# samll_car.net
KiCad netlist of a schematic drawn in Altium Designer
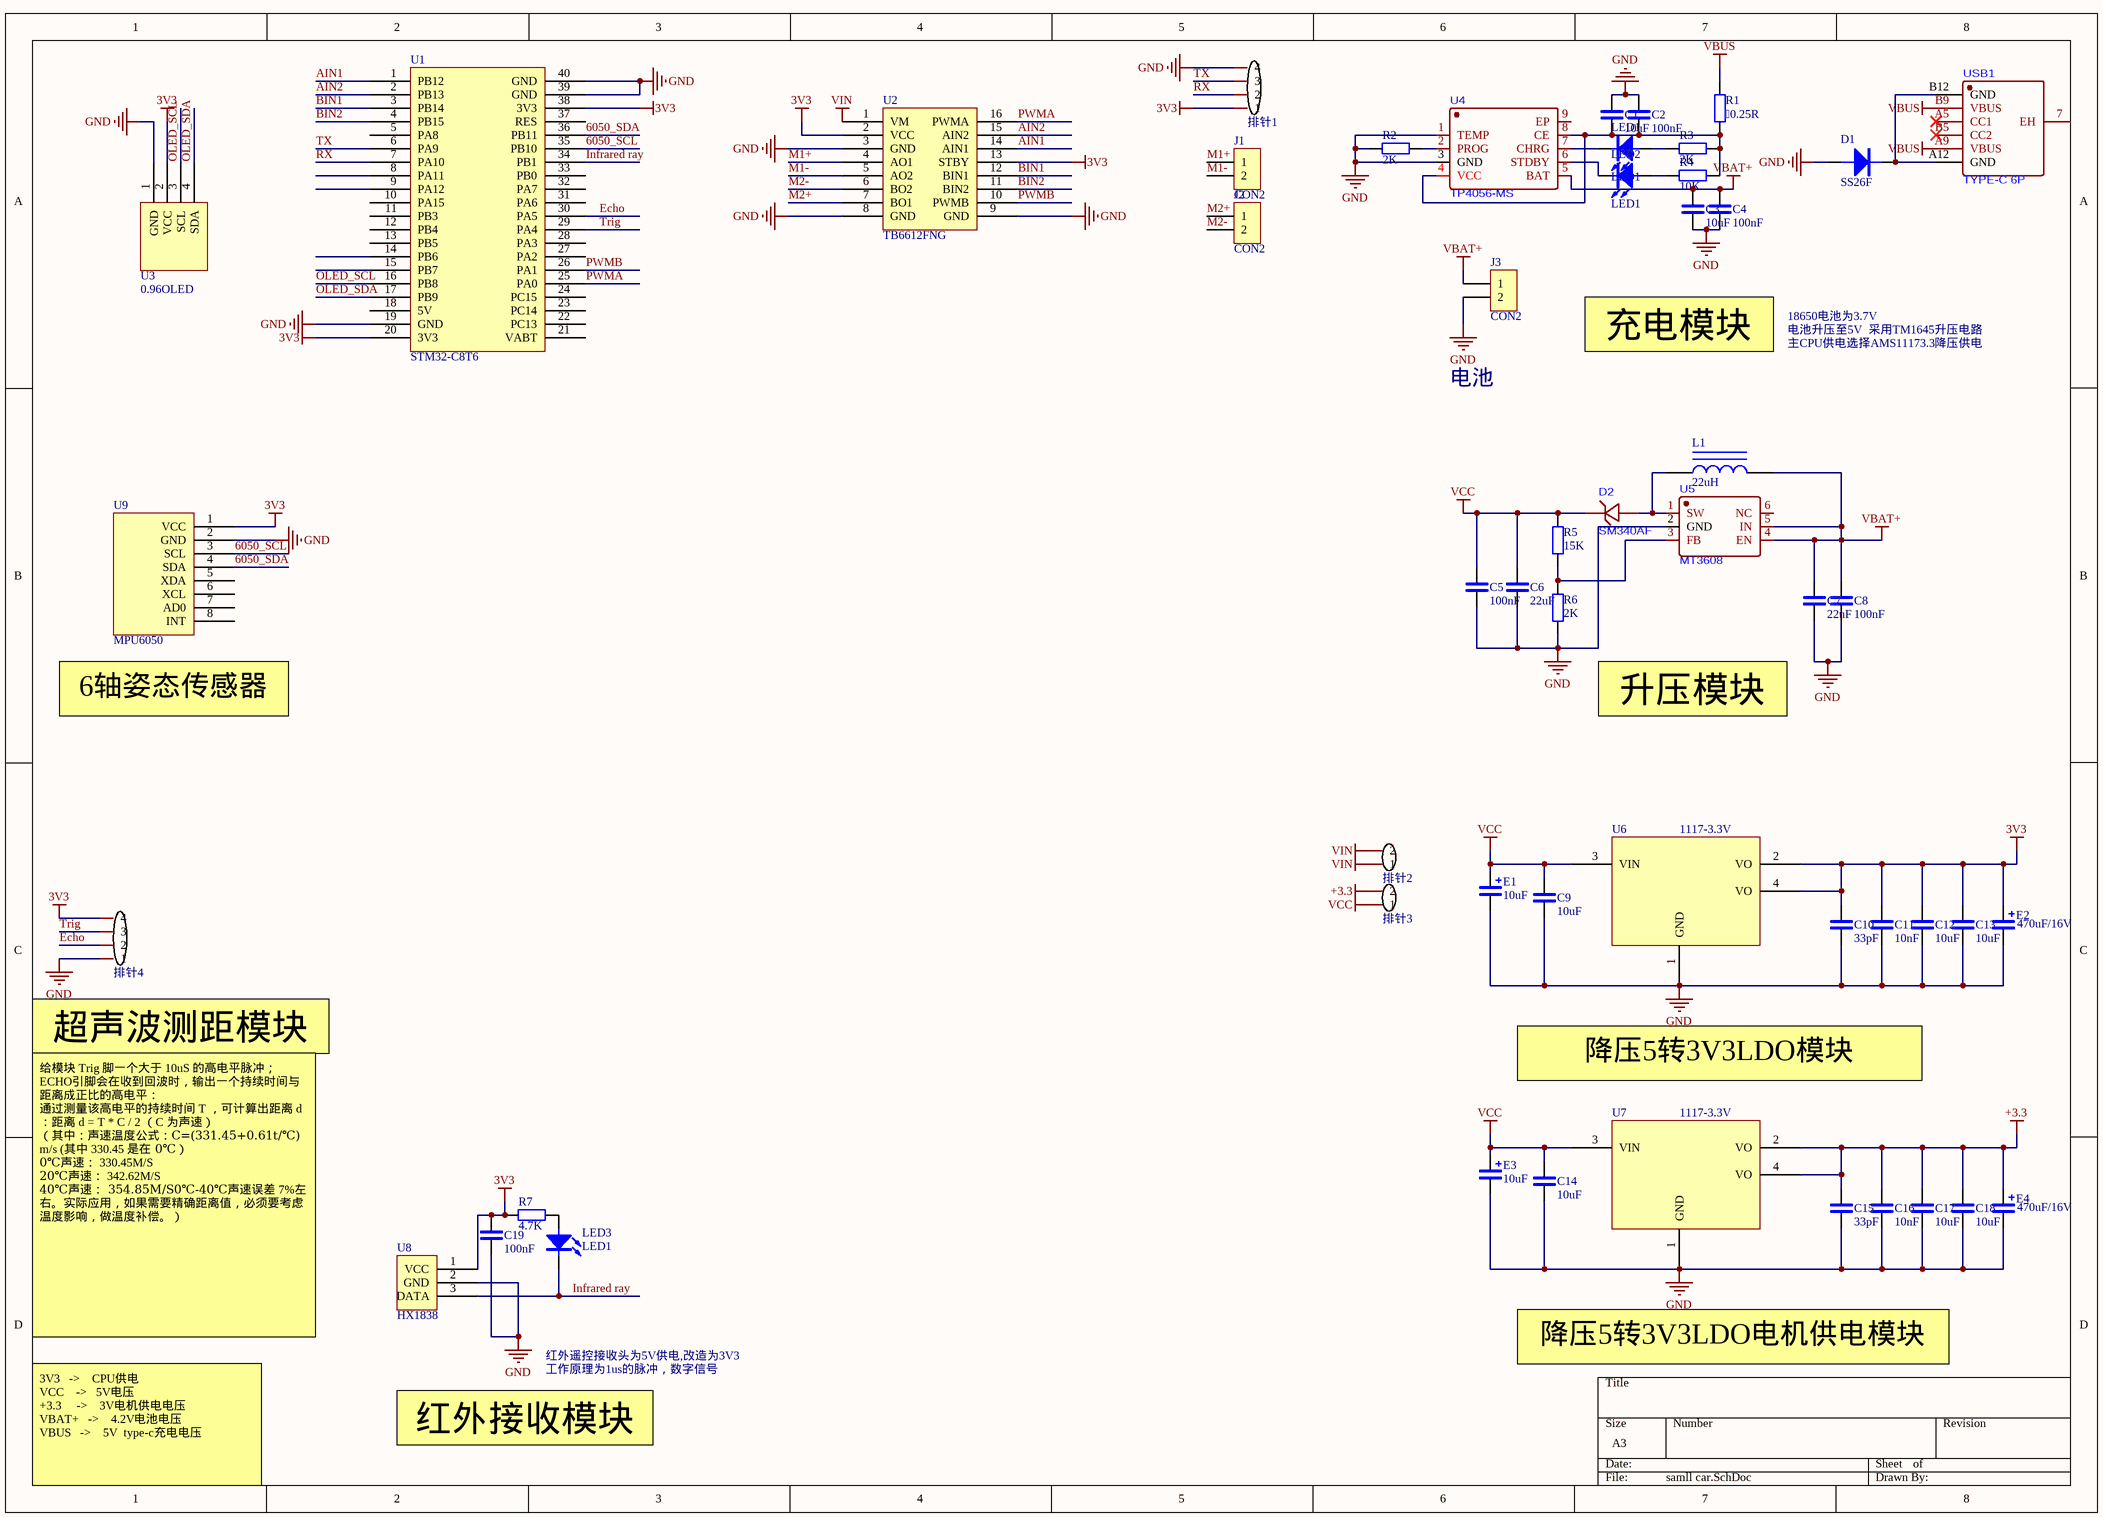
[diagram p0: samll car.SchDoc]

(export (version "E")
  (design (tool "Eeschema 10.0.6"))
  (components
    (comp (ref "C1")
      (value "10uF")
      (footprint "C0603")
      (description "Capacitor")
      (libsource (lib "General") (part "CAP"))
    )
    (comp (ref "C2")
      (value "100nF")
      (footprint "C0603")
      (description "Capacitor")
      (libsource (lib "General") (part "CAP"))
    )
    (comp (ref "C3")
      (value "10uF")
      (footprint "C0603")
      (description "Capacitor")
      (libsource (lib "General") (part "CAP"))
    )
    (comp (ref "C4")
      (value "100nF")
      (footprint "C0603")
      (description "Capacitor")
      (libsource (lib "General") (part "CAP"))
    )
    (comp (ref "C5")
      (value "100nF")
      (footprint "C0603")
      (description "Capacitor")
      (libsource (lib "General") (part "CAP"))
    )
    (comp (ref "C6")
      (value "22uF")
      (footprint "C0603")
      (description "Capacitor")
      (libsource (lib "General") (part "CAP"))
    )
    (comp (ref "C7")
      (value "22uF")
      (footprint "C0603")
      (description "Capacitor")
      (libsource (lib "General") (part "CAP"))
    )
    (comp (ref "C8")
      (value "100nF")
      (footprint "C0603")
      (description "Capacitor")
      (libsource (lib "General") (part "CAP"))
    )
    (comp (ref "C9")
      (value "10uF")
      (footprint "C0603")
      (description "Capacitor")
      (libsource (lib "General") (part "CAP"))
    )
    (comp (ref "C10")
      (value "33pF")
      (footprint "C0603")
      (description "Capacitor")
      (libsource (lib "General") (part "CAP"))
    )
    (comp (ref "C11")
      (value "10nF")
      (footprint "C0603")
      (description "Capacitor")
      (libsource (lib "General") (part "CAP"))
    )
    (comp (ref "C12")
      (value "10uF")
      (footprint "C0603")
      (description "Capacitor")
      (libsource (lib "General") (part "CAP"))
    )
    (comp (ref "C13")
      (value "10uF")
      (footprint "C0603")
      (description "Capacitor")
      (libsource (lib "General") (part "CAP"))
    )
    (comp (ref "C14")
      (value "10uF")
      (footprint "C0603")
      (description "Capacitor")
      (libsource (lib "General") (part "CAP"))
    )
    (comp (ref "C15")
      (value "33pF")
      (footprint "C0603")
      (description "Capacitor")
      (libsource (lib "General") (part "CAP"))
    )
    (comp (ref "C16")
      (value "10nF")
      (footprint "C0603")
      (description "Capacitor")
      (libsource (lib "General") (part "CAP"))
    )
    (comp (ref "C17")
      (value "10uF")
      (footprint "C0603")
      (description "Capacitor")
      (libsource (lib "General") (part "CAP"))
    )
    (comp (ref "C18")
      (value "10uF")
      (footprint "C0603")
      (description "Capacitor")
      (libsource (lib "General") (part "CAP"))
    )
    (comp (ref "C19")
      (value "100nF")
      (footprint "C0603")
      (description "Capacitor")
      (libsource (lib "General") (part "CAP"))
    )
    (comp (ref "D1")
      (value "SS26F")
      (footprint "SMAF")
      (description "Diode")
      (libsource (lib "莫尼库") (part "1N4007"))
    )
    (comp (ref "D2") (value "SM340AF") (footprint "SMA-FL-RD") (libsource (lib "莫尼库") (part "F1M")))
    (comp (ref "E1")
      (value "10uF")
      (footprint "CAP-TANTALUM-A")
      (description "Tantalum Capacitor")
      (libsource (lib "General") (part "CAP-TANTALUM"))
    )
    (comp (ref "E2")
      (value "470uF/16V")
      (footprint "CAP-TH_BD6.0-P2.50-D0.5-FD")
      (description "Tantalum Capacitor")
      (libsource (lib "General") (part "CAP-TANTALUM"))
    )
    (comp (ref "E3")
      (value "10uF")
      (footprint "CAP-TANTALUM-A")
      (description "Tantalum Capacitor")
      (libsource (lib "General") (part "CAP-TANTALUM"))
    )
    (comp (ref "E4")
      (value "470uF/16V")
      (footprint "CAP-TH_BD6.0-P2.50-D0.5-FD")
      (description "Tantalum Capacitor")
      (libsource (lib "General") (part "CAP-TANTALUM"))
    )
    (comp (ref "J1")
      (value "CON2")
      (footprint "XH2.54-2PZZ")
      (description "Connector")
      (libsource (lib "莫尼库") (part "CON2"))
    )
    (comp (ref "J2")
      (value "CON2")
      (footprint "XH2.54-2PZZ")
      (description "Connector")
      (libsource (lib "莫尼库") (part "CON2"))
    )
    (comp (ref "J3")
      (value "CON2")
      (footprint "XH2.54-2PZZ")
      (description "Connector")
      (libsource (lib "莫尼库") (part "CON2"))
    )
    (comp (ref "L1")
      (value "22uH")
      (footprint "IND-SMD_L5.0-W5.0")
      (description "Magnetic-Core Inductor")
      (fields (field (name "PUBLISHER") "Altium Limited"))
      (libsource (lib "莫尼库") (part "Inductor Iron"))
    )
    (comp (ref "LED1")
      (value "LED1")
      (footprint "LED-0603")
      (description "单色发光二极管")
      (libsource (lib "莫尼库") (part "LED1"))
    )
    (comp (ref "LED2")
      (value "LED1")
      (footprint "LED-0603")
      (description "单色发光二极管")
      (libsource (lib "莫尼库") (part "LED1"))
    )
    (comp (ref "LED3")
      (value "LED1")
      (footprint "LED-0603")
      (description "单色发光二极管")
      (libsource (lib "莫尼库") (part "LED1"))
    )
    (comp (ref "R1")
      (value "0.25R")
      (footprint "R1206")
      (description "Resistor")
      (libsource (lib "General") (part "RES"))
    )
    (comp (ref "R2")
      (value "2K")
      (footprint "R0603")
      (description "Resistor")
      (libsource (lib "") (part "RES_2"))
    )
    (comp (ref "R3")
      (value "2K")
      (footprint "R0603")
      (description "Resistor")
      (libsource (lib "") (part "RES_1"))
    )
    (comp (ref "R4")
      (value "10K")
      (footprint "R0603")
      (description "Resistor")
      (libsource (lib "") (part "RES_1"))
    )
    (comp (ref "R5")
      (value "15K")
      (footprint "R0603")
      (description "Resistor")
      (libsource (lib "General") (part "RES"))
    )
    (comp (ref "R6")
      (value "2K")
      (footprint "R0603")
      (description "Resistor")
      (libsource (lib "General") (part "RES"))
    )
    (comp (ref "R7")
      (value "4.7K")
      (footprint "R0603")
      (description "Resistor")
      (libsource (lib "") (part "RES_1"))
    )
    (comp (ref "U1")
      (value "STM32-C8T6")
      (footprint "STM32-C8T6")
      (libsource (lib "small car") (part "STM32-C8T6"))
    )
    (comp (ref "U2")
      (value "TB6612FNG")
      (footprint "TB6612FNG")
      (libsource (lib "small car") (part "TB6612FNG"))
    )
    (comp (ref "U3")
      (value "0.96OLED")
      (footprint "0.96OLED")
      (libsource (lib "small car") (part "0.96OLED"))
    )
    (comp (ref "U4") (value "TP4056-MS") (footprint "SOP-8-TL-EP") (libsource (lib "莫尼库") (part "TP4056-MS")))
    (comp (ref "U5") (value "MT3608") (footprint "SOT-23-6") (libsource (lib "莫尼库") (part "MT3608")))
    (comp (ref "U6")
      (value "1117-3.3V")
      (footprint "SOT-223")
      (description "Linear Regulator")
      (libsource (lib "General") (part "1117"))
    )
    (comp (ref "U7")
      (value "1117-3.3V")
      (footprint "SOT-223")
      (description "Linear Regulator")
      (libsource (lib "General") (part "1117"))
    )
    (comp (ref "U8") (value "HX1838") (footprint "VS/HX1838B") (libsource (lib "small car") (part "HX1838")))
    (comp (ref "U9") (value "MPU6050") (footprint "MPU6050") (libsource (lib "small car") (part "MPU6050")))
    (comp (ref "USB1") (value "TYPE-C 6P") (footprint "TYPE-C-6P") (libsource (lib "莫尼库") (part "TYPE-C 6P")))
    (comp (ref "排针1") (value "4P 排针") (footprint "XH2.54-1*4") (libsource (lib "莫尼库") (part "4P 排针")))
    (comp (ref "排针2") (value "2P 排针") (footprint "XH2.54-1*2") (libsource (lib "莫尼库") (part "2P 排针")))
    (comp (ref "排针3") (value "2P 排针") (footprint "XH2.54-1*2") (libsource (lib "莫尼库") (part "2P 排针")))
    (comp (ref "排针4") (value "4P 排针") (footprint "XH2.54-1*4") (libsource (lib "莫尼库") (part "4P 排针")))
  )
  (nets
    (net (code "1") (name "+3.3") (class "Default")
      (node (ref "C15") (pin "2") (pinfunction "2_2") (pintype "passive"))
      (node (ref "C16") (pin "2") (pinfunction "2_2") (pintype "passive"))
      (node (ref "C17") (pin "2") (pinfunction "2_2") (pintype "passive"))
      (node (ref "C18") (pin "2") (pinfunction "2_2") (pintype "passive"))
      (node (ref "E4") (pin "1") (pinfunction "1_1") (pintype "passive"))
      (node (ref "U7") (pin "2") (pinfunction "VO_2") (pintype "passive"))
      (node (ref "U7") (pin "4") (pinfunction "VO_4") (pintype "passive"))
      (node (ref "排针3") (pin "2") (pinfunction "2_2") (pintype "passive"))
    )
    (net (code "2") (name "/6050_SCL") (class "Default")
      (node (ref "U1") (pin "35") (pinfunction "PB10_35") (pintype "passive"))
      (node (ref "U9") (pin "3") (pinfunction "SCL_3") (pintype "passive"))
    )
    (net (code "3") (name "/6050_SDA") (class "Default")
      (node (ref "U1") (pin "36") (pinfunction "PB11_36") (pintype "passive"))
      (node (ref "U9") (pin "4") (pinfunction "SDA_4") (pintype "passive"))
    )
    (net (code "4") (name "/AIN1") (class "Default")
      (node (ref "U1") (pin "1") (pinfunction "PB12_1") (pintype "passive"))
      (node (ref "U2") (pin "14") (pinfunction "AIN1_14") (pintype "passive"))
    )
    (net (code "5") (name "/AIN2") (class "Default")
      (node (ref "U1") (pin "2") (pinfunction "PB13_2") (pintype "passive"))
      (node (ref "U2") (pin "15") (pinfunction "AIN2_15") (pintype "passive"))
    )
    (net (code "6") (name "/BIN1") (class "Default")
      (node (ref "U1") (pin "3") (pinfunction "PB14_3") (pintype "passive"))
      (node (ref "U2") (pin "12") (pinfunction "BIN1_12") (pintype "passive"))
    )
    (net (code "7") (name "/BIN2") (class "Default")
      (node (ref "U1") (pin "4") (pinfunction "PB15_4") (pintype "passive"))
      (node (ref "U2") (pin "11") (pinfunction "BIN2_11") (pintype "passive"))
    )
    (net (code "8") (name "/Echo") (class "Default")
      (node (ref "U1") (pin "30") (pinfunction "PA5_30") (pintype "passive"))
      (node (ref "排针4") (pin "2") (pinfunction "2_2") (pintype "passive"))
    )
    (net (code "9") (name "/Infrared ray") (class "Default")
      (node (ref "LED3") (pin "2") (pinfunction "C_2") (pintype "passive"))
      (node (ref "U1") (pin "34") (pinfunction "PB1_34") (pintype "passive"))
      (node (ref "U8") (pin "3") (pinfunction "DATA_3") (pintype "passive"))
    )
    (net (code "10") (name "/M1+") (class "Default")
      (node (ref "J1") (pin "1") (pinfunction "1_1") (pintype "passive"))
      (node (ref "U2") (pin "4") (pinfunction "AO1_4") (pintype "passive"))
    )
    (net (code "11") (name "/M1-") (class "Default")
      (node (ref "J1") (pin "2") (pinfunction "2_2") (pintype "passive"))
      (node (ref "U2") (pin "5") (pinfunction "AO2_5") (pintype "passive"))
    )
    (net (code "12") (name "/M2+") (class "Default")
      (node (ref "J2") (pin "1") (pinfunction "1_1") (pintype "passive"))
      (node (ref "U2") (pin "7") (pinfunction "BO1_7") (pintype "passive"))
    )
    (net (code "13") (name "/M2-") (class "Default")
      (node (ref "J2") (pin "2") (pinfunction "2_2") (pintype "passive"))
      (node (ref "U2") (pin "6") (pinfunction "BO2_6") (pintype "passive"))
    )
    (net (code "14") (name "/OLED_SCL") (class "Default")
      (node (ref "U1") (pin "16") (pinfunction "PB8_16") (pintype "passive"))
      (node (ref "U3") (pin "3") (pinfunction "SCL_3") (pintype "passive"))
    )
    (net (code "15") (name "/OLED_SDA") (class "Default")
      (node (ref "U1") (pin "17") (pinfunction "PB9_17") (pintype "passive"))
      (node (ref "U3") (pin "4") (pinfunction "SDA_4") (pintype "passive"))
    )
    (net (code "16") (name "/PWMA") (class "Default")
      (node (ref "U1") (pin "25") (pinfunction "PA0_25") (pintype "passive"))
      (node (ref "U2") (pin "16") (pinfunction "PWMA_16") (pintype "passive"))
    )
    (net (code "17") (name "/PWMB") (class "Default")
      (node (ref "U1") (pin "26") (pinfunction "PA1_26") (pintype "passive"))
      (node (ref "U2") (pin "10") (pinfunction "PWMB_10") (pintype "passive"))
    )
    (net (code "18") (name "/RX") (class "Default")
      (node (ref "U1") (pin "7") (pinfunction "PA10_7") (pintype "passive"))
      (node (ref "排针1") (pin "2") (pinfunction "2_2") (pintype "passive"))
    )
    (net (code "19") (name "/TX") (class "Default")
      (node (ref "U1") (pin "6") (pinfunction "PA9_6") (pintype "passive"))
      (node (ref "排针1") (pin "3") (pinfunction "3_3") (pintype "passive"))
    )
    (net (code "20") (name "/Trig") (class "Default")
      (node (ref "U1") (pin "29") (pinfunction "PA4_29") (pintype "passive"))
      (node (ref "排针4") (pin "3") (pinfunction "3_3") (pintype "passive"))
    )
    (net (code "21") (name "3V3") (class "Default")
      (node (ref "C10") (pin "2") (pinfunction "2_2") (pintype "passive"))
      (node (ref "C11") (pin "2") (pinfunction "2_2") (pintype "passive"))
      (node (ref "C12") (pin "2") (pinfunction "2_2") (pintype "passive"))
      (node (ref "C13") (pin "2") (pinfunction "2_2") (pintype "passive"))
      (node (ref "C19") (pin "1") (pinfunction "1_1") (pintype "passive"))
      (node (ref "E2") (pin "1") (pinfunction "1_1") (pintype "passive"))
      (node (ref "R7") (pin "2") (pinfunction "2_2") (pintype "passive"))
      (node (ref "U1") (pin "20") (pinfunction "3V3_20") (pintype "passive"))
      (node (ref "U1") (pin "38") (pinfunction "3V3_38") (pintype "passive"))
      (node (ref "U2") (pin "13") (pinfunction "STBY_13") (pintype "passive"))
      (node (ref "U2") (pin "2") (pinfunction "VCC_2") (pintype "passive"))
      (node (ref "U3") (pin "2") (pinfunction "VCC_2") (pintype "passive"))
      (node (ref "U6") (pin "2") (pinfunction "VO_2") (pintype "passive"))
      (node (ref "U6") (pin "4") (pinfunction "VO_4") (pintype "passive"))
      (node (ref "U8") (pin "1") (pinfunction "VCC_1") (pintype "passive"))
      (node (ref "U9") (pin "1") (pinfunction "VCC_1") (pintype "passive"))
      (node (ref "排针1") (pin "1") (pinfunction "1_1") (pintype "passive"))
      (node (ref "排针4") (pin "4") (pinfunction "4_4") (pintype "passive"))
    )
    (net (code "22") (name "GND") (class "Default")
      (node (ref "C1") (pin "1") (pinfunction "1_1") (pintype "passive"))
      (node (ref "C10") (pin "1") (pinfunction "1_1") (pintype "passive"))
      (node (ref "C11") (pin "1") (pinfunction "1_1") (pintype "passive"))
      (node (ref "C12") (pin "1") (pinfunction "1_1") (pintype "passive"))
      (node (ref "C13") (pin "1") (pinfunction "1_1") (pintype "passive"))
      (node (ref "C14") (pin "1") (pinfunction "1_1") (pintype "passive"))
      (node (ref "C15") (pin "1") (pinfunction "1_1") (pintype "passive"))
      (node (ref "C16") (pin "1") (pinfunction "1_1") (pintype "passive"))
      (node (ref "C17") (pin "1") (pinfunction "1_1") (pintype "passive"))
      (node (ref "C18") (pin "1") (pinfunction "1_1") (pintype "passive"))
      (node (ref "C19") (pin "2") (pinfunction "2_2") (pintype "passive"))
      (node (ref "C2") (pin "1") (pinfunction "1_1") (pintype "passive"))
      (node (ref "C3") (pin "2") (pinfunction "2_2") (pintype "passive"))
      (node (ref "C4") (pin "2") (pinfunction "2_2") (pintype "passive"))
      (node (ref "C5") (pin "2") (pinfunction "2_2") (pintype "passive"))
      (node (ref "C6") (pin "2") (pinfunction "2_2") (pintype "passive"))
      (node (ref "C7") (pin "2") (pinfunction "2_2") (pintype "passive"))
      (node (ref "C8") (pin "2") (pinfunction "2_2") (pintype "passive"))
      (node (ref "C9") (pin "1") (pinfunction "1_1") (pintype "passive"))
      (node (ref "D1") (pin "1") (pinfunction "1_1") (pintype "passive"))
      (node (ref "E1") (pin "2") (pinfunction "2_2") (pintype "passive"))
      (node (ref "E2") (pin "2") (pinfunction "2_2") (pintype "passive"))
      (node (ref "E3") (pin "2") (pinfunction "2_2") (pintype "passive"))
      (node (ref "E4") (pin "2") (pinfunction "2_2") (pintype "passive"))
      (node (ref "J3") (pin "2") (pinfunction "2_2") (pintype "passive"))
      (node (ref "R2") (pin "1") (pinfunction "1_1") (pintype "passive"))
      (node (ref "R6") (pin "2") (pinfunction "2_2") (pintype "passive"))
      (node (ref "U1") (pin "19") (pinfunction "GND_19") (pintype "passive"))
      (node (ref "U1") (pin "39") (pinfunction "GND_39") (pintype "passive"))
      (node (ref "U1") (pin "40") (pinfunction "GND_40") (pintype "passive"))
      (node (ref "U2") (pin "3") (pinfunction "GND_3") (pintype "passive"))
      (node (ref "U2") (pin "8") (pinfunction "GND_8") (pintype "passive"))
      (node (ref "U2") (pin "9") (pinfunction "GND_9") (pintype "passive"))
      (node (ref "U3") (pin "1") (pinfunction "GND_1") (pintype "passive"))
      (node (ref "U4") (pin "1") (pinfunction "TEMP_1") (pintype "passive"))
      (node (ref "U4") (pin "3") (pinfunction "GND_3") (pintype "passive"))
      (node (ref "U5") (pin "2") (pinfunction "GND_2") (pintype "passive"))
      (node (ref "U6") (pin "1") (pinfunction "GND_1") (pintype "passive"))
      (node (ref "U7") (pin "1") (pinfunction "GND_1") (pintype "passive"))
      (node (ref "U8") (pin "2") (pinfunction "GND_2") (pintype "passive"))
      (node (ref "U9") (pin "2") (pinfunction "GND_2") (pintype "passive"))
      (node (ref "排针1") (pin "4") (pinfunction "4_4") (pintype "passive"))
      (node (ref "排针4") (pin "1") (pinfunction "1_1") (pintype "passive"))
    )
    (net (code "23") (name "Net-(D1-Pad2)") (class "Default")
      (node (ref "D1") (pin "2") (pinfunction "2_2") (pintype "passive"))
      (node (ref "USB1") (pin "A12") (pinfunction "GND_A12") (pintype "passive"))
      (node (ref "USB1") (pin "B12") (pinfunction "GND_B12") (pintype "passive"))
    )
    (net (code "24") (name "Net-(D2-A)") (class "Default")
      (node (ref "D2") (pin "2") (pinfunction "A_2") (pintype "passive"))
      (node (ref "L1") (pin "1") (pinfunction "1_1") (pintype "passive"))
      (node (ref "U5") (pin "1") (pinfunction "SW_1") (pintype "passive"))
    )
    (net (code "25") (name "Net-(LED1-A)") (class "Default")
      (node (ref "LED1") (pin "1") (pinfunction "A_1") (pintype "passive"))
      (node (ref "R3") (pin "2") (pinfunction "2_2") (pintype "passive"))
    )
    (net (code "26") (name "Net-(LED1-C)") (class "Default")
      (node (ref "LED1") (pin "2") (pinfunction "C_2") (pintype "passive"))
      (node (ref "U4") (pin "7") (pinfunction "CHRG_7") (pintype "passive"))
    )
    (net (code "27") (name "Net-(LED2-A)") (class "Default")
      (node (ref "LED2") (pin "1") (pinfunction "A_1") (pintype "passive"))
      (node (ref "R4") (pin "2") (pinfunction "2_2") (pintype "passive"))
    )
    (net (code "28") (name "Net-(LED2-C)") (class "Default")
      (node (ref "LED2") (pin "2") (pinfunction "C_2") (pintype "passive"))
      (node (ref "U4") (pin "6") (pinfunction "STDBY_6") (pintype "passive"))
    )
    (net (code "29") (name "Net-(LED3-A)") (class "Default")
      (node (ref "LED3") (pin "1") (pinfunction "A_1") (pintype "passive"))
      (node (ref "R7") (pin "1") (pinfunction "1_1") (pintype "passive"))
    )
    (net (code "30") (name "Net-(U4-CE)") (class "Default")
      (node (ref "C1") (pin "2") (pinfunction "2_2") (pintype "passive"))
      (node (ref "C2") (pin "2") (pinfunction "2_2") (pintype "passive"))
      (node (ref "R1") (pin "2") (pinfunction "2_2") (pintype "passive"))
      (node (ref "R3") (pin "1") (pinfunction "1_1") (pintype "passive"))
      (node (ref "R4") (pin "1") (pinfunction "1_1") (pintype "passive"))
      (node (ref "U4") (pin "4") (pinfunction "VCC_4") (pintype "passive"))
      (node (ref "U4") (pin "8") (pinfunction "CE_8") (pintype "passive"))
    )
    (net (code "31") (name "Net-(U4-PROG)") (class "Default")
      (node (ref "R2") (pin "2") (pinfunction "2_2") (pintype "passive"))
      (node (ref "U4") (pin "2") (pinfunction "PROG_2") (pintype "passive"))
    )
    (net (code "32") (name "Net-(U5-FB)") (class "Default")
      (node (ref "R5") (pin "2") (pinfunction "2_2") (pintype "passive"))
      (node (ref "R6") (pin "1") (pinfunction "1_1") (pintype "passive"))
      (node (ref "U5") (pin "3") (pinfunction "FB_3") (pintype "passive"))
    )
    (net (code "33") (name "VBAT+") (class "Default")
      (node (ref "C3") (pin "1") (pinfunction "1_1") (pintype "passive"))
      (node (ref "C4") (pin "1") (pinfunction "1_1") (pintype "passive"))
      (node (ref "C7") (pin "1") (pinfunction "1_1") (pintype "passive"))
      (node (ref "C8") (pin "1") (pinfunction "1_1") (pintype "passive"))
      (node (ref "J3") (pin "1") (pinfunction "1_1") (pintype "passive"))
      (node (ref "L1") (pin "2") (pinfunction "2_2") (pintype "passive"))
      (node (ref "U4") (pin "5") (pinfunction "BAT_5") (pintype "passive"))
      (node (ref "U5") (pin "4") (pinfunction "EN_4") (pintype "passive"))
      (node (ref "U5") (pin "5") (pinfunction "IN_5") (pintype "passive"))
    )
    (net (code "34") (name "VBUS") (class "Default")
      (node (ref "R1") (pin "1") (pinfunction "1_1") (pintype "passive"))
      (node (ref "USB1") (pin "A9") (pinfunction "VBUS_A9") (pintype "passive"))
      (node (ref "USB1") (pin "B9") (pinfunction "VBUS_B9") (pintype "passive"))
    )
    (net (code "35") (name "VCC") (class "Default")
      (node (ref "C14") (pin "2") (pinfunction "2_2") (pintype "passive"))
      (node (ref "C5") (pin "1") (pinfunction "1_1") (pintype "passive"))
      (node (ref "C6") (pin "1") (pinfunction "1_1") (pintype "passive"))
      (node (ref "C9") (pin "2") (pinfunction "2_2") (pintype "passive"))
      (node (ref "D2") (pin "1") (pinfunction "C_1") (pintype "passive"))
      (node (ref "E1") (pin "1") (pinfunction "1_1") (pintype "passive"))
      (node (ref "E3") (pin "1") (pinfunction "1_1") (pintype "passive"))
      (node (ref "R5") (pin "1") (pinfunction "1_1") (pintype "passive"))
      (node (ref "U6") (pin "3") (pinfunction "VIN_3") (pintype "passive"))
      (node (ref "U7") (pin "3") (pinfunction "VIN_3") (pintype "passive"))
      (node (ref "排针3") (pin "1") (pinfunction "1_1") (pintype "passive"))
    )
    (net (code "36") (name "VIN") (class "Default")
      (node (ref "U2") (pin "1") (pinfunction "VM_1") (pintype "passive"))
      (node (ref "排针2") (pin "1") (pinfunction "1_1") (pintype "passive"))
      (node (ref "排针2") (pin "2") (pinfunction "2_2") (pintype "passive"))
    )
    (net (code "37") (name "unconnected-(U1-5V-Pad18)") (class "Default")
      (node (ref "U1") (pin "18") (pinfunction "5V_18") (pintype "passive"))
    )
    (net (code "38") (name "unconnected-(U1-PA2-Pad27)") (class "Default")
      (node (ref "U1") (pin "27") (pinfunction "PA2_27") (pintype "passive"))
    )
    (net (code "39") (name "unconnected-(U1-PA3-Pad28)") (class "Default")
      (node (ref "U1") (pin "28") (pinfunction "PA3_28") (pintype "passive"))
    )
    (net (code "40") (name "unconnected-(U1-PA6-Pad31)") (class "Default")
      (node (ref "U1") (pin "31") (pinfunction "PA6_31") (pintype "passive"))
    )
    (net (code "41") (name "unconnected-(U1-PA7-Pad32)") (class "Default")
      (node (ref "U1") (pin "32") (pinfunction "PA7_32") (pintype "passive"))
    )
    (net (code "42") (name "unconnected-(U1-PA8-Pad5)") (class "Default")
      (node (ref "U1") (pin "5") (pinfunction "PA8_5") (pintype "passive"))
    )
    (net (code "43") (name "unconnected-(U1-PA11-Pad8)") (class "Default")
      (node (ref "U1") (pin "8") (pinfunction "PA11_8") (pintype "passive"))
    )
    (net (code "44") (name "unconnected-(U1-PA12-Pad9)") (class "Default")
      (node (ref "U1") (pin "9") (pinfunction "PA12_9") (pintype "passive"))
    )
    (net (code "45") (name "unconnected-(U1-PA15-Pad10)") (class "Default")
      (node (ref "U1") (pin "10") (pinfunction "PA15_10") (pintype "passive"))
    )
    (net (code "46") (name "unconnected-(U1-PB0-Pad33)") (class "Default")
      (node (ref "U1") (pin "33") (pinfunction "PB0_33") (pintype "passive"))
    )
    (net (code "47") (name "unconnected-(U1-PB3-Pad11)") (class "Default")
      (node (ref "U1") (pin "11") (pinfunction "PB3_11") (pintype "passive"))
    )
    (net (code "48") (name "unconnected-(U1-PB4-Pad12)") (class "Default")
      (node (ref "U1") (pin "12") (pinfunction "PB4_12") (pintype "passive"))
    )
    (net (code "49") (name "unconnected-(U1-PB5-Pad13)") (class "Default")
      (node (ref "U1") (pin "13") (pinfunction "PB5_13") (pintype "passive"))
    )
    (net (code "50") (name "unconnected-(U1-PB6-Pad14)") (class "Default")
      (node (ref "U1") (pin "14") (pinfunction "PB6_14") (pintype "passive"))
    )
    (net (code "51") (name "unconnected-(U1-PB7-Pad15)") (class "Default")
      (node (ref "U1") (pin "15") (pinfunction "PB7_15") (pintype "passive"))
    )
    (net (code "52") (name "unconnected-(U1-PC13-Pad22)") (class "Default")
      (node (ref "U1") (pin "22") (pinfunction "PC13_22") (pintype "passive"))
    )
    (net (code "53") (name "unconnected-(U1-PC14-Pad23)") (class "Default")
      (node (ref "U1") (pin "23") (pinfunction "PC14_23") (pintype "passive"))
    )
    (net (code "54") (name "unconnected-(U1-PC15-Pad24)") (class "Default")
      (node (ref "U1") (pin "24") (pinfunction "PC15_24") (pintype "passive"))
    )
    (net (code "55") (name "unconnected-(U1-RES-Pad37)") (class "Default")
      (node (ref "U1") (pin "37") (pinfunction "RES_37") (pintype "passive"))
    )
    (net (code "56") (name "unconnected-(U1-VABT-Pad21)") (class "Default")
      (node (ref "U1") (pin "21") (pinfunction "VABT_21") (pintype "passive"))
    )
    (net (code "57") (name "unconnected-(U4-EP-Pad9)") (class "Default")
      (node (ref "U4") (pin "9") (pinfunction "EP_9") (pintype "passive"))
    )
    (net (code "58") (name "unconnected-(U5-NC-Pad6)") (class "Default")
      (node (ref "U5") (pin "6") (pinfunction "NC_6") (pintype "passive"))
    )
    (net (code "59") (name "unconnected-(U9-AD0-Pad7)") (class "Default")
      (node (ref "U9") (pin "7") (pinfunction "AD0_7") (pintype "passive"))
    )
    (net (code "60") (name "unconnected-(U9-INT-Pad8)") (class "Default")
      (node (ref "U9") (pin "8") (pinfunction "INT_8") (pintype "passive"))
    )
    (net (code "61") (name "unconnected-(U9-XCL-Pad6)") (class "Default")
      (node (ref "U9") (pin "6") (pinfunction "XCL_6") (pintype "passive"))
    )
    (net (code "62") (name "unconnected-(U9-XDA-Pad5)") (class "Default")
      (node (ref "U9") (pin "5") (pinfunction "XDA_5") (pintype "passive"))
    )
    (net (code "63") (name "unconnected-(USB1-CC1-PadA5)") (class "Default")
      (node (ref "USB1") (pin "A5") (pinfunction "CC1_A5") (pintype "passive+no_connect"))
    )
    (net (code "64") (name "unconnected-(USB1-CC2-PadB5)") (class "Default")
      (node (ref "USB1") (pin "B5") (pinfunction "CC2_B5") (pintype "passive+no_connect"))
    )
    (net (code "65") (name "unconnected-(USB1-EH-Pad7)") (class "Default")
      (node (ref "USB1") (pin "7") (pinfunction "EH_7") (pintype "passive"))
    )
  )
)
